# WAKEUP.net
KiCad netlist of a schematic drawn in Altium Designer
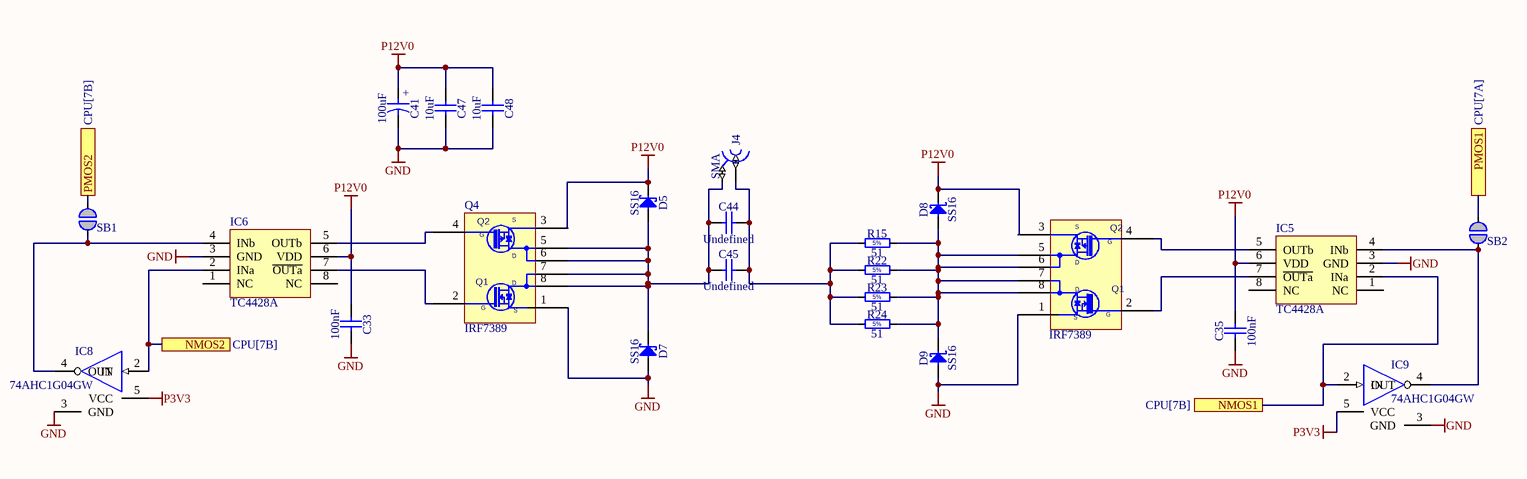
[diagram p0: WAKEUP.SchDoc]

(export (version "E")
  (design (tool "Eeschema 10.0.6"))
  (components
    (comp (ref "C33")
      (value "100nF")
      (footprint "CAPC1608X87N")
      (description "Non-polarised capacitor")
      (fields
        (field (name "PART NUMBER") "CC0603_100NF_50V_10%_X7R")
        (field (name "VOLTAGE") "50V")
        (field (name "AUTHOR") "CERN DEM JLC")
      )
      (libsource (lib "Capacitors") (part "Capacitor - non polarized"))
    )
    (comp (ref "C35")
      (value "100nF")
      (footprint "CAPC1608X87N")
      (description "Non-polarised capacitor")
      (fields
        (field (name "PART NUMBER") "CC0603_100NF_50V_10%_X7R")
        (field (name "VOLTAGE") "50V")
        (field (name "AUTHOR") "CERN DEM JLC")
      )
      (libsource (lib "Capacitors") (part "Capacitor - non polarized"))
    )
    (comp (ref "C41")
      (value "100uF")
      (footprint "CAPAE660X540N")
      (description "Polarised capacitor")
      (fields
        (field (name "PART NUMBER") "CAE660-540_100UF_16V_20%")
        (field (name "VOLTAGE") "16V")
        (field (name "AUTHOR") "CERN DEM JLC")
      )
      (libsource (lib "Capacitors") (part "Capacitor - polarized"))
    )
    (comp (ref "C44")
      (value "Undefined")
      (footprint "CAPC2012X135N")
      (description "Non-polarised capacitor")
      (fields (field (name "PART NUMBER") "CC0805_NO-VALUE") (field (name "AUTHOR") "CERN DEM JLC"))
      (libsource (lib "Capacitors") (part "Capacitor - non polarized"))
    )
    (comp (ref "C45")
      (value "Undefined")
      (footprint "CAPC2012X135N")
      (description "Non-polarised capacitor")
      (fields (field (name "PART NUMBER") "CC0805_NO-VALUE") (field (name "AUTHOR") "CERN DEM JLC"))
      (libsource (lib "Capacitors") (part "Capacitor - non polarized"))
    )
    (comp (ref "C47")
      (value "10uF")
      (footprint "CAPC3216X140N")
      (description "Non-polarised capacitor")
      (fields
        (field (name "PART NUMBER") "CC1206_10UF_16V_10%_X7R")
        (field (name "VOLTAGE") "16V")
        (field (name "AUTHOR") "CERN DEM JLC")
      )
      (libsource (lib "Capacitors") (part "Capacitor - non polarized"))
    )
    (comp (ref "C48")
      (value "10uF")
      (footprint "CAPC3216X140N")
      (description "Non-polarised capacitor")
      (fields
        (field (name "PART NUMBER") "CC1206_10UF_16V_10%_X7R")
        (field (name "VOLTAGE") "16V")
        (field (name "AUTHOR") "CERN DEM JLC")
      )
      (libsource (lib "Capacitors") (part "Capacitor - non polarized"))
    )
    (comp (ref "D5")
      (value "SS16")
      (footprint "DIOM5127X229N")
      (description "Schottky Diode")
      (fields
        (field (name "VOLTAGE") "60V")
        (field (name "POWER") "1A")
        (field (name "AUTHOR") "CERN DEM JLC")
      )
      (libsource (lib "ICs And Semiconductors") (part "Diode Schottky"))
    )
    (comp (ref "D7")
      (value "SS16")
      (footprint "DIOM5127X229N")
      (description "Schottky Diode")
      (fields
        (field (name "VOLTAGE") "60V")
        (field (name "POWER") "1A")
        (field (name "AUTHOR") "CERN DEM JLC")
      )
      (libsource (lib "ICs And Semiconductors") (part "Diode Schottky"))
    )
    (comp (ref "D8")
      (value "SS16")
      (footprint "DIOM5127X229N")
      (description "Schottky Diode")
      (fields
        (field (name "VOLTAGE") "60V")
        (field (name "POWER") "1A")
        (field (name "AUTHOR") "CERN DEM JLC")
      )
      (libsource (lib "ICs And Semiconductors") (part "Diode Schottky"))
    )
    (comp (ref "D9")
      (value "SS16")
      (footprint "DIOM5127X229N")
      (description "Schottky Diode")
      (fields
        (field (name "VOLTAGE") "60V")
        (field (name "POWER") "1A")
        (field (name "AUTHOR") "CERN DEM JLC")
      )
      (libsource (lib "ICs And Semiconductors") (part "Diode Schottky"))
    )
    (comp (ref "IC5")
      (value "TC4428A")
      (footprint "SO-8")
      (description "MOSFET Driver")
      (libsource (lib "LIBRARY_SCH") (part "DRV_TC4428A"))
    )
    (comp (ref "IC6")
      (value "TC4428A")
      (footprint "SO-8")
      (description "MOSFET Driver")
      (libsource (lib "") (part "DRV_TC4428A_1"))
    )
    (comp (ref "IC8")
      (value "74AHC1G04GW")
      (footprint "SOT65P212X110-5N")
      (description "Single Inverter Buffer")
      (fields (field (name "MANUFACTURER") "NXP SEMICONDUCTORS") (field (name "AUTHOR") "CERN DEM JLC"))
      (libsource (lib "ICs And Semiconductors") (part "741G04"))
    )
    (comp (ref "IC9")
      (value "74AHC1G04GW")
      (footprint "SOT65P212X110-5N")
      (description "Single Inverter Buffer")
      (fields (field (name "MANUFACTURER") "NXP SEMICONDUCTORS") (field (name "AUTHOR") "CERN DEM JLC"))
      (libsource (lib "ICs And Semiconductors") (part "741G04"))
    )
    (comp (ref "J4")
      (value "SMA")
      (footprint "HUBER-SUHNER_85_SMA-50-0-101/111_NE")
      (fields
        (field (name "PART NUMBER") "HUBER-SUHNER_85_SMA-50-0-101/111_NE")
        (field (name "MANUFACTURER") "HUBER+SUHNER")
        (field (name "MANUFACTURER PART NUMBER") "85_SMA-50-0-101/111_NE")
        (field (name "AUTHOR") "CERN DEM JLC")
      )
      (libsource (lib "Connectors") (part "Coax_1Female_1Shield"))
    )
    (comp (ref "Q4") (value "IRF7389") (footprint "SO-8") (libsource (lib "irf") (part "IRF7389")))
    (comp (ref "Q5") (value "IRF7389") (footprint "SO-8") (libsource (lib "irf") (part "IRF7389")))
    (comp (ref "R15")
      (value "51")
      (footprint "RESC6331X80N")
      (description "Resistor - 5%")
      (fields
        (field (name "PART NUMBER") "R2512_51R_5%_2W_200PPM_BOURNS_CRM2512")
        (field (name "POWER") "2W")
        (field (name "AUTHOR") "CERN DEM JLC")
      )
      (libsource (lib "Resistors") (part "Resistor - 5%"))
    )
    (comp (ref "R22")
      (value "51")
      (footprint "RESC6331X80N")
      (description "Resistor - 5%")
      (fields
        (field (name "PART NUMBER") "R2512_51R_5%_2W_200PPM_BOURNS_CRM2512")
        (field (name "POWER") "2W")
        (field (name "AUTHOR") "CERN DEM JLC")
      )
      (libsource (lib "Resistors") (part "Resistor - 5%"))
    )
    (comp (ref "R23")
      (value "51")
      (footprint "RESC6331X80N")
      (description "Resistor - 5%")
      (fields
        (field (name "PART NUMBER") "R2512_51R_5%_2W_200PPM_BOURNS_CRM2512")
        (field (name "POWER") "2W")
        (field (name "AUTHOR") "CERN DEM JLC")
      )
      (libsource (lib "Resistors") (part "Resistor - 5%"))
    )
    (comp (ref "R24")
      (value "51")
      (footprint "RESC6331X80N")
      (description "Resistor - 5%")
      (fields
        (field (name "PART NUMBER") "R2512_51R_5%_2W_200PPM_BOURNS_CRM2512")
        (field (name "POWER") "2W")
        (field (name "AUTHOR") "CERN DEM JLC")
      )
      (libsource (lib "Resistors") (part "Resistor - 5%"))
    )
    (comp (ref "SB1")
      (value "Solderbridge")
      (footprint "Solderbridge")
      (fields (field (name "PUBLISHER") "Nordic Semiconductor"))
      (libsource (lib "pca10040") (part "SOLDERBRIDGE"))
    )
    (comp (ref "SB2")
      (value "Solderbridge")
      (footprint "Solderbridge")
      (fields (field (name "PUBLISHER") "Nordic Semiconductor"))
      (libsource (lib "pca10040") (part "SOLDERBRIDGE"))
    )
  )
  (nets
    (net (code "1") (name "/NMOS1") (class "Default")
      (node (ref "IC5") (pin "2") (pinfunction "INa_2") (pintype "passive"))
      (node (ref "IC9") (pin "2") (pinfunction "IN_2") (pintype "input"))
    )
    (net (code "2") (name "/NMOS2") (class "Default")
      (node (ref "IC6") (pin "2") (pinfunction "INa_2") (pintype "passive"))
      (node (ref "IC8") (pin "2") (pinfunction "IN_2") (pintype "input"))
    )
    (net (code "3") (name "/PMOS1") (class "Default")
      (node (ref "SB2") (pin "1") (pinfunction "0_1") (pintype "passive"))
    )
    (net (code "4") (name "/PMOS2") (class "Default")
      (node (ref "SB1") (pin "1") (pinfunction "0_1") (pintype "passive"))
    )
    (net (code "5") (name "GND") (class "Default")
      (node (ref "C33") (pin "1") (pinfunction "1_1") (pintype "passive"))
      (node (ref "C35") (pin "1") (pinfunction "1_1") (pintype "passive"))
      (node (ref "C41") (pin "2") (pinfunction "2_2") (pintype "passive"))
      (node (ref "C47") (pin "2") (pinfunction "2_2") (pintype "passive"))
      (node (ref "C48") (pin "2") (pinfunction "2_2") (pintype "passive"))
      (node (ref "D7") (pin "2") (pinfunction "A_2") (pintype "passive"))
      (node (ref "D9") (pin "2") (pinfunction "A_2") (pintype "passive"))
      (node (ref "IC5") (pin "3") (pinfunction "GND_3") (pintype "passive"))
      (node (ref "IC6") (pin "3") (pinfunction "GND_3") (pintype "passive"))
      (node (ref "IC8") (pin "3") (pinfunction "GND_3") (pintype "power_in"))
      (node (ref "IC9") (pin "3") (pinfunction "GND_3") (pintype "power_in"))
      (node (ref "Q4") (pin "1") (pinfunction "S-N_1") (pintype "passive"))
      (node (ref "Q5") (pin "1") (pinfunction "S-N_1") (pintype "passive"))
    )
    (net (code "6") (name "Net-(C44-Pad2)") (class "Default")
      (node (ref "C44") (pin "2") (pinfunction "2_2") (pintype "passive"))
      (node (ref "C45") (pin "2") (pinfunction "2_2") (pintype "passive"))
      (node (ref "J4") (pin "1") (pinfunction "1_1") (pintype "bidirectional"))
      (node (ref "R15") (pin "1") (pinfunction "1_1") (pintype "passive"))
      (node (ref "R22") (pin "1") (pinfunction "1_1") (pintype "passive"))
      (node (ref "R23") (pin "1") (pinfunction "1_1") (pintype "passive"))
      (node (ref "R24") (pin "1") (pinfunction "1_1") (pintype "passive"))
    )
    (net (code "7") (name "Net-(D5-A)") (class "Default")
      (node (ref "C44") (pin "1") (pinfunction "1_1") (pintype "passive"))
      (node (ref "C45") (pin "1") (pinfunction "1_1") (pintype "passive"))
      (node (ref "D5") (pin "2") (pinfunction "A_2") (pintype "passive"))
      (node (ref "D7") (pin "1") (pinfunction "C_1") (pintype "passive"))
      (node (ref "J4") (pin "2") (pinfunction "2_2") (pintype "bidirectional"))
      (node (ref "Q4") (pin "5") (pinfunction "D-P_5") (pintype "passive"))
      (node (ref "Q4") (pin "6") (pinfunction "D-P_6") (pintype "passive"))
      (node (ref "Q4") (pin "7") (pinfunction "D-N_7") (pintype "passive"))
      (node (ref "Q4") (pin "8") (pinfunction "D-N_8") (pintype "passive"))
    )
    (net (code "8") (name "Net-(D8-A)") (class "Default")
      (node (ref "D8") (pin "2") (pinfunction "A_2") (pintype "passive"))
      (node (ref "D9") (pin "1") (pinfunction "C_1") (pintype "passive"))
      (node (ref "Q5") (pin "5") (pinfunction "D-P_5") (pintype "passive"))
      (node (ref "Q5") (pin "6") (pinfunction "D-P_6") (pintype "passive"))
      (node (ref "Q5") (pin "7") (pinfunction "D-N_7") (pintype "passive"))
      (node (ref "Q5") (pin "8") (pinfunction "D-N_8") (pintype "passive"))
      (node (ref "R15") (pin "2") (pinfunction "2_2") (pintype "passive"))
      (node (ref "R22") (pin "2") (pinfunction "2_2") (pintype "passive"))
      (node (ref "R23") (pin "2") (pinfunction "2_2") (pintype "passive"))
      (node (ref "R24") (pin "2") (pinfunction "2_2") (pintype "passive"))
    )
    (net (code "9") (name "Net-(IC5-INb)") (class "Default")
      (node (ref "IC5") (pin "4") (pinfunction "INb_4") (pintype "passive"))
      (node (ref "IC9") (pin "4") (pinfunction "OUT_4") (pintype "open_collector"))
      (node (ref "SB2") (pin "2") (pinfunction "1_2") (pintype "passive"))
    )
    (net (code "10") (name "Net-(IC5-OUTb)") (class "Default")
      (node (ref "IC5") (pin "5") (pinfunction "OUTb_5") (pintype "passive"))
      (node (ref "Q5") (pin "4") (pinfunction "G-P_4") (pintype "passive"))
    )
    (net (code "11") (name "Net-(IC5-~{OUTa})") (class "Default")
      (node (ref "IC5") (pin "7") (pinfunction "~{OUTa}_7") (pintype "passive"))
      (node (ref "Q5") (pin "2") (pinfunction "G-N_2") (pintype "passive"))
    )
    (net (code "12") (name "Net-(IC6-INb)") (class "Default")
      (node (ref "IC6") (pin "4") (pinfunction "INb_4") (pintype "passive"))
      (node (ref "IC8") (pin "4") (pinfunction "OUT_4") (pintype "open_collector"))
      (node (ref "SB1") (pin "2") (pinfunction "1_2") (pintype "passive"))
    )
    (net (code "13") (name "Net-(IC6-OUTb)") (class "Default")
      (node (ref "IC6") (pin "5") (pinfunction "OUTb_5") (pintype "passive"))
      (node (ref "Q4") (pin "4") (pinfunction "G-P_4") (pintype "passive"))
    )
    (net (code "14") (name "Net-(IC6-~{OUTa})") (class "Default")
      (node (ref "IC6") (pin "7") (pinfunction "~{OUTa}_7") (pintype "passive"))
      (node (ref "Q4") (pin "2") (pinfunction "G-N_2") (pintype "passive"))
    )
    (net (code "15") (name "P3V3") (class "Default")
      (node (ref "IC8") (pin "5") (pinfunction "VCC_5") (pintype "power_in"))
      (node (ref "IC9") (pin "5") (pinfunction "VCC_5") (pintype "power_in"))
    )
    (net (code "16") (name "P12V0") (class "Default")
      (node (ref "C33") (pin "2") (pinfunction "2_2") (pintype "passive"))
      (node (ref "C35") (pin "2") (pinfunction "2_2") (pintype "passive"))
      (node (ref "C41") (pin "1") (pinfunction "1_1") (pintype "passive"))
      (node (ref "C47") (pin "1") (pinfunction "1_1") (pintype "passive"))
      (node (ref "C48") (pin "1") (pinfunction "1_1") (pintype "passive"))
      (node (ref "D5") (pin "1") (pinfunction "C_1") (pintype "passive"))
      (node (ref "D8") (pin "1") (pinfunction "C_1") (pintype "passive"))
      (node (ref "IC5") (pin "6") (pinfunction "VDD_6") (pintype "passive"))
      (node (ref "IC6") (pin "6") (pinfunction "VDD_6") (pintype "passive"))
      (node (ref "Q4") (pin "3") (pinfunction "S-P_3") (pintype "passive"))
      (node (ref "Q5") (pin "3") (pinfunction "S-P_3") (pintype "passive"))
    )
    (net (code "17") (name "unconnected-(IC5-NC-Pad1)") (class "Default")
      (node (ref "IC5") (pin "1") (pinfunction "NC_1") (pintype "passive"))
    )
    (net (code "18") (name "unconnected-(IC5-NC-Pad8)") (class "Default")
      (node (ref "IC5") (pin "8") (pinfunction "NC_8") (pintype "passive"))
    )
    (net (code "19") (name "unconnected-(IC6-NC-Pad1)") (class "Default")
      (node (ref "IC6") (pin "1") (pinfunction "NC_1") (pintype "passive"))
    )
    (net (code "20") (name "unconnected-(IC6-NC-Pad8)") (class "Default")
      (node (ref "IC6") (pin "8") (pinfunction "NC_8") (pintype "passive"))
    )
  )
)
